# TSOC_Teensy3X.net
KiCad netlist of a schematic drawn in EAGLE
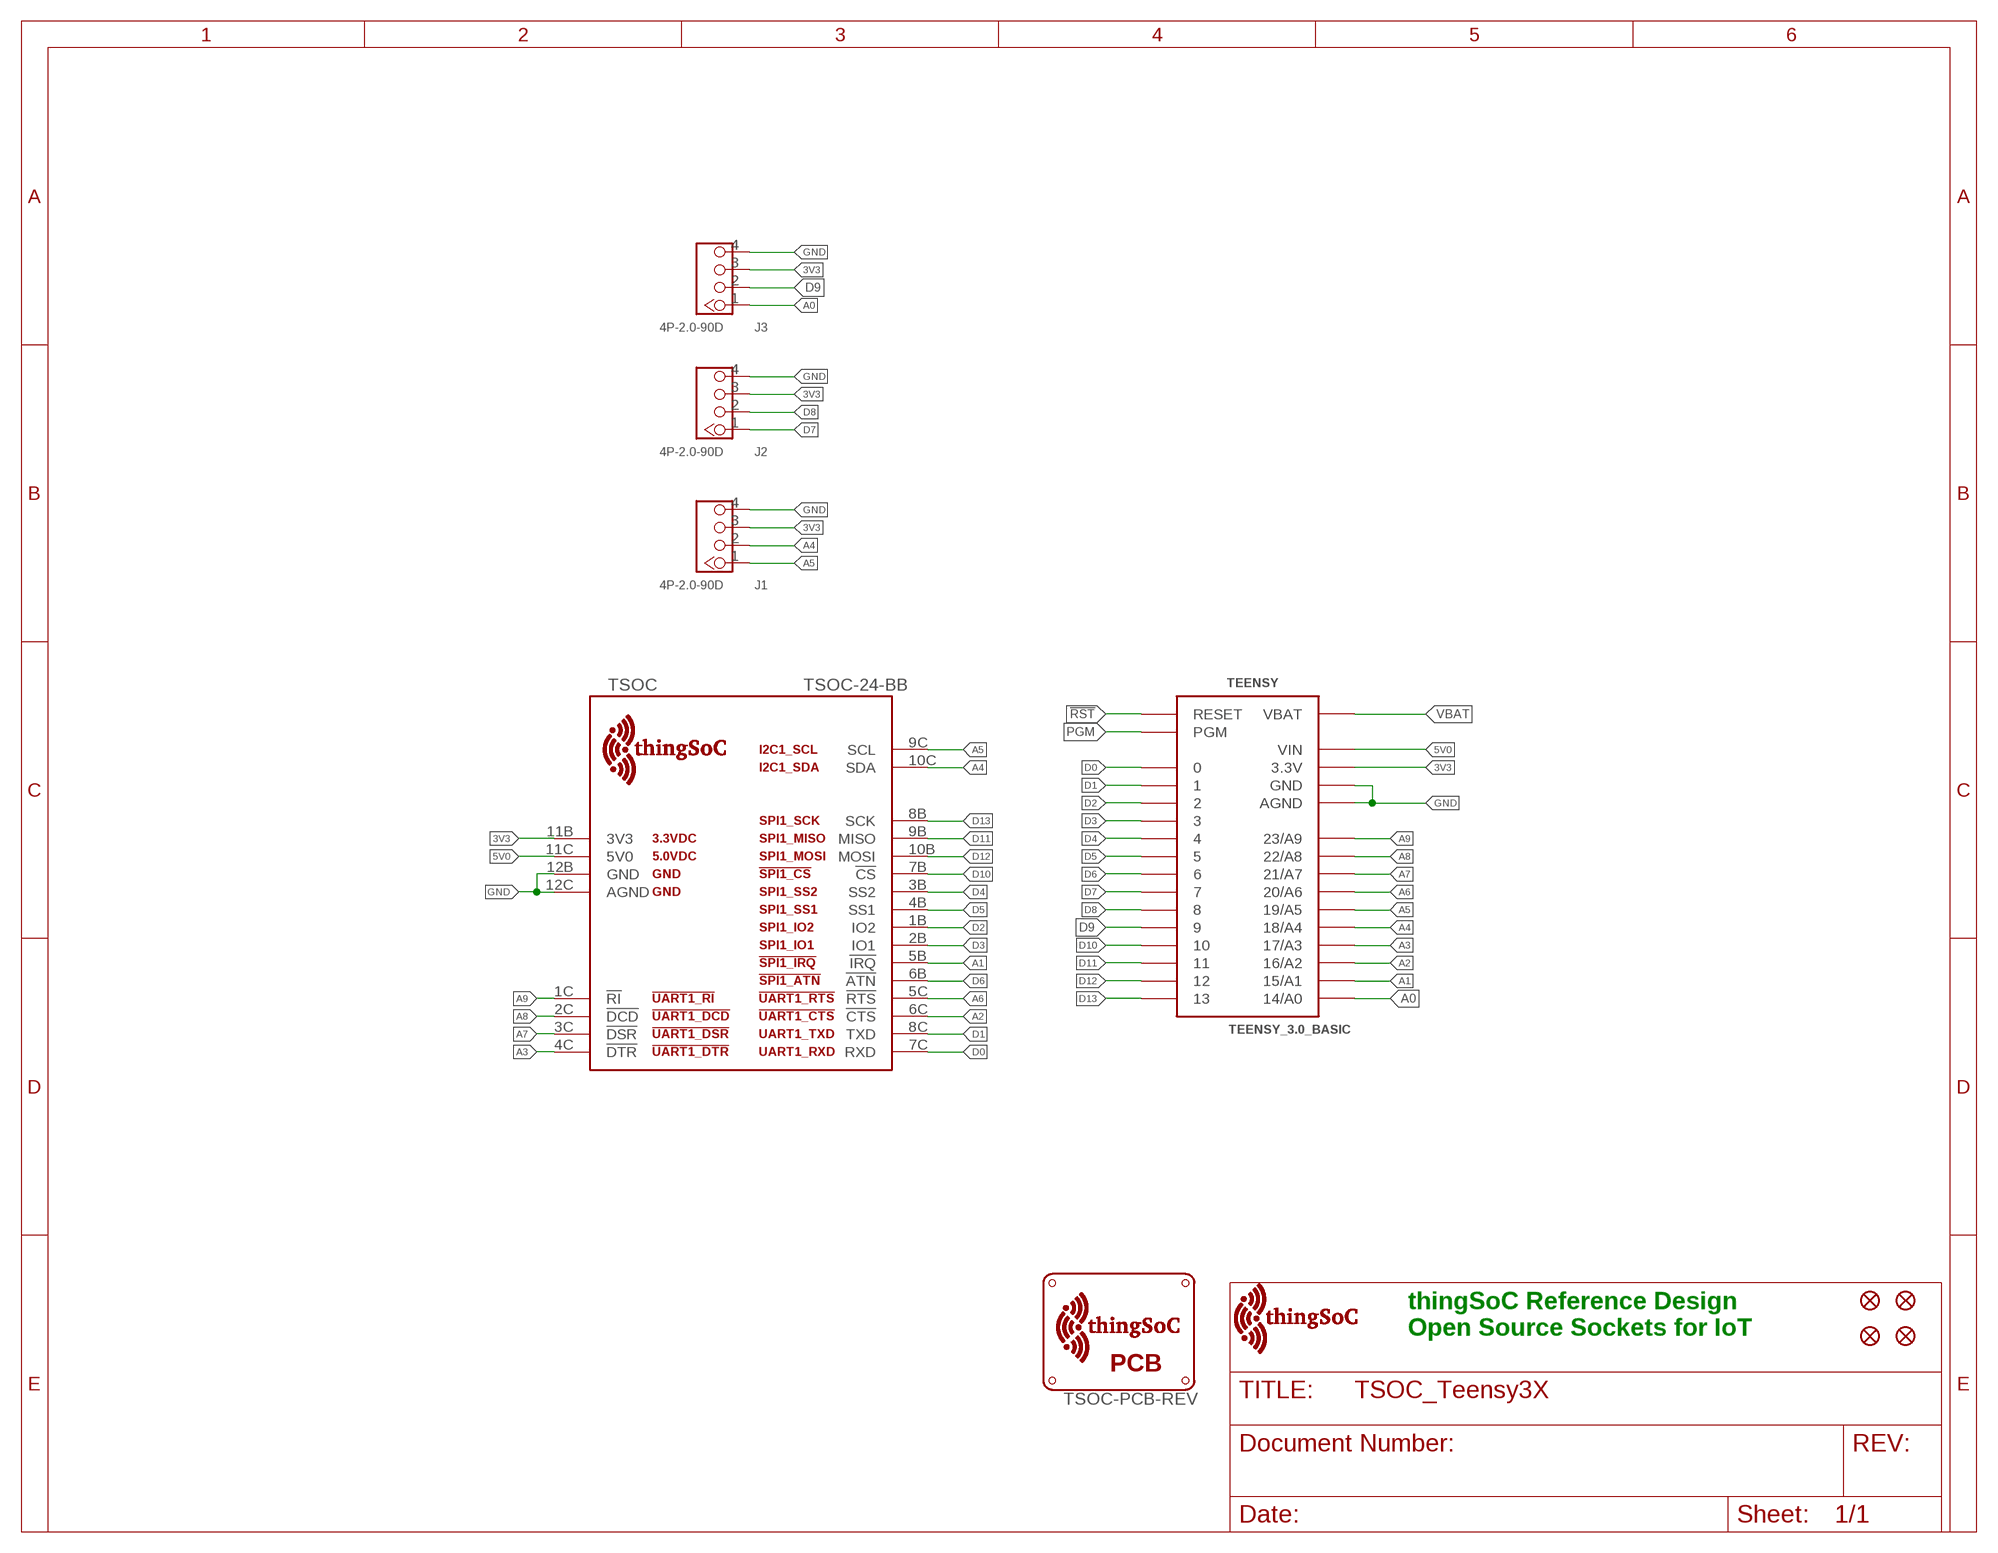
[diagram p0: schematic, sheet 1]

(export (version "E")
  (design (tool "Eeschema 10.0.6"))
  (components
    (comp (ref "FID1")
      (value "FIDUCIALUFIDUCIAL")
      (footprint "eagle-import:MICRO-FIDUCIAL")
      (libsource (lib "eagle-import") (part "FIDUCIALUFIDUCIAL"))
    )
    (comp (ref "FID2")
      (value "FIDUCIALUFIDUCIAL")
      (footprint "eagle-import:MICRO-FIDUCIAL")
      (libsource (lib "eagle-import") (part "FIDUCIALUFIDUCIAL"))
    )
    (comp (ref "FID3")
      (value "FIDUCIALUFIDUCIAL")
      (footprint "eagle-import:MICRO-FIDUCIAL")
      (libsource (lib "eagle-import") (part "FIDUCIALUFIDUCIAL"))
    )
    (comp (ref "FID4")
      (value "FIDUCIALUFIDUCIAL")
      (footprint "eagle-import:MICRO-FIDUCIAL")
      (libsource (lib "eagle-import") (part "FIDUCIALUFIDUCIAL"))
    )
    (comp (ref "J1")
      (value "4P-2.0-90D")
      (footprint "eagle-import:HW4-2.0-90D")
      (libsource (lib "eagle-import") (part "GROVE-CONNECTOR-DIP-90D(4P-2.0)"))
    )
    (comp (ref "J2")
      (value "4P-2.0-90D")
      (footprint "eagle-import:HW4-2.0-90D")
      (libsource (lib "eagle-import") (part "GROVE-CONNECTOR-DIP-90D(4P-2.0)"))
    )
    (comp (ref "J3")
      (value "4P-2.0-90D")
      (footprint "eagle-import:HW4-2.0-90D")
      (libsource (lib "eagle-import") (part "GROVE-CONNECTOR-DIP-90D(4P-2.0)"))
    )
    (comp (ref "TEENSY")
      (value "TEENSY_3.0_BASIC")
      (footprint "eagle-import:TEENSY_3.0_BASIC")
      (libsource (lib "eagle-import") (part "TEENSY_3.0_BASIC"))
    )
    (comp (ref "TSOC")
      (value "TSOC-24-BB")
      (footprint "eagle-import:TSOC-BB-S24")
      (libsource (lib "eagle-import") (part "TSOC-24-BB"))
    )
    (comp (ref "U$2")
      (value "TSOC-PCB-REV")
      (footprint "eagle-import:TSOC-BB-BRD-PLUS-CUT-REV")
      (libsource (lib "eagle-import") (part "TSOC-PCB-REV"))
    )
    (comp (ref "U$5")
      (value "TSOC-LOGO-LRG")
      (footprint "eagle-import:TSOC-LOGO-LRG")
      (libsource (lib "eagle-import") (part "TSOC-LOGO-LRG"))
    )
  )
  (nets
    (net (code "1") (name "/~{RST}") (class "Default")
      (node (ref "TEENSY") (pin "RESET") (pinfunction "RESET_RESET") (pintype "bidirectional"))
    )
    (net (code "2") (name "3V3") (class "Default")
      (node (ref "J1") (pin "3") (pinfunction "3_3") (pintype "bidirectional"))
      (node (ref "J2") (pin "3") (pinfunction "3_3") (pintype "bidirectional"))
      (node (ref "J3") (pin "3") (pinfunction "3_3") (pintype "bidirectional"))
      (node (ref "TEENSY") (pin "3.3V") (pinfunction "3.3V_3.3V") (pintype "power_in"))
      (node (ref "TEENSY") (pin "3.3V1") (pinfunction "3.3V_3.3V1") (pintype "power_in"))
      (node (ref "TSOC") (pin "11B") (pinfunction "3V3_11B") (pintype "bidirectional"))
    )
    (net (code "3") (name "5V0") (class "Default")
      (node (ref "TEENSY") (pin "VIN") (pinfunction "VIN_VIN") (pintype "power_in"))
      (node (ref "TSOC") (pin "11C") (pinfunction "5V0_11C") (pintype "bidirectional"))
    )
    (net (code "4") (name "A0") (class "Default")
      (node (ref "J3") (pin "1") (pinfunction "1_1") (pintype "bidirectional"))
      (node (ref "TEENSY") (pin "14/A0") (pinfunction "14/A0_14/A0") (pintype "bidirectional"))
    )
    (net (code "5") (name "A1") (class "Default")
      (node (ref "TEENSY") (pin "15/A1") (pinfunction "15/A1_15/A1") (pintype "bidirectional"))
      (node (ref "TSOC") (pin "5B") (pinfunction "~{IRQ}_5B") (pintype "bidirectional"))
    )
    (net (code "6") (name "A2") (class "Default")
      (node (ref "TEENSY") (pin "16/A2") (pinfunction "16/A2_16/A2") (pintype "bidirectional"))
      (node (ref "TSOC") (pin "6C") (pinfunction "~{CTS}_6C") (pintype "bidirectional"))
    )
    (net (code "7") (name "A3") (class "Default")
      (node (ref "TEENSY") (pin "17/A3") (pinfunction "17/A3_17/A3") (pintype "bidirectional"))
      (node (ref "TSOC") (pin "4C") (pinfunction "~{DTR}_4C") (pintype "bidirectional"))
    )
    (net (code "8") (name "A4") (class "Default")
      (node (ref "J1") (pin "2") (pinfunction "2_2") (pintype "bidirectional"))
      (node (ref "TEENSY") (pin "18/A4") (pinfunction "18/A4_18/A4") (pintype "bidirectional"))
      (node (ref "TSOC") (pin "10C") (pinfunction "SDA_10C") (pintype "bidirectional"))
    )
    (net (code "9") (name "A5") (class "Default")
      (node (ref "J1") (pin "1") (pinfunction "1_1") (pintype "bidirectional"))
      (node (ref "TEENSY") (pin "19/A5") (pinfunction "19/A5_19/A5") (pintype "bidirectional"))
      (node (ref "TSOC") (pin "9C") (pinfunction "SCL_9C") (pintype "bidirectional"))
    )
    (net (code "10") (name "A6") (class "Default")
      (node (ref "TEENSY") (pin "20/A6") (pinfunction "20/A6_20/A6") (pintype "bidirectional"))
      (node (ref "TSOC") (pin "5C") (pinfunction "~{RTS}_5C") (pintype "bidirectional"))
    )
    (net (code "11") (name "A7") (class "Default")
      (node (ref "TEENSY") (pin "21/A7") (pinfunction "21/A7_21/A7") (pintype "bidirectional"))
      (node (ref "TSOC") (pin "3C") (pinfunction "~{DSR}_3C") (pintype "bidirectional"))
    )
    (net (code "12") (name "A8") (class "Default")
      (node (ref "TEENSY") (pin "22/A8") (pinfunction "22/A8_22/A8") (pintype "bidirectional"))
      (node (ref "TSOC") (pin "2C") (pinfunction "~{DCD}_2C") (pintype "bidirectional"))
    )
    (net (code "13") (name "A9") (class "Default")
      (node (ref "TEENSY") (pin "23/A9") (pinfunction "23/A9_23/A9") (pintype "bidirectional"))
      (node (ref "TSOC") (pin "1C") (pinfunction "~{RI}_1C") (pintype "bidirectional"))
    )
    (net (code "14") (name "D0") (class "Default")
      (node (ref "TEENSY") (pin "0") (pinfunction "0_0") (pintype "bidirectional"))
      (node (ref "TSOC") (pin "7C") (pinfunction "RXD_7C") (pintype "bidirectional"))
    )
    (net (code "15") (name "D1") (class "Default")
      (node (ref "TEENSY") (pin "1") (pinfunction "1_1") (pintype "bidirectional"))
      (node (ref "TSOC") (pin "8C") (pinfunction "TXD_8C") (pintype "bidirectional"))
    )
    (net (code "16") (name "D2") (class "Default")
      (node (ref "TEENSY") (pin "2") (pinfunction "2_2") (pintype "bidirectional"))
      (node (ref "TSOC") (pin "1B") (pinfunction "IO2_1B") (pintype "bidirectional"))
    )
    (net (code "17") (name "D3") (class "Default")
      (node (ref "TEENSY") (pin "3") (pinfunction "3_3") (pintype "bidirectional"))
      (node (ref "TSOC") (pin "2B") (pinfunction "IO1_2B") (pintype "bidirectional"))
    )
    (net (code "18") (name "D4") (class "Default")
      (node (ref "TEENSY") (pin "4") (pinfunction "4_4") (pintype "bidirectional"))
      (node (ref "TSOC") (pin "3B") (pinfunction "SS2_3B") (pintype "bidirectional"))
    )
    (net (code "19") (name "D5") (class "Default")
      (node (ref "TEENSY") (pin "5") (pinfunction "5_5") (pintype "bidirectional"))
      (node (ref "TSOC") (pin "4B") (pinfunction "SS1_4B") (pintype "bidirectional"))
    )
    (net (code "20") (name "D6") (class "Default")
      (node (ref "TEENSY") (pin "6") (pinfunction "6_6") (pintype "bidirectional"))
      (node (ref "TSOC") (pin "6B") (pinfunction "~{ATN}_6B") (pintype "bidirectional"))
    )
    (net (code "21") (name "D7") (class "Default")
      (node (ref "J2") (pin "1") (pinfunction "1_1") (pintype "bidirectional"))
      (node (ref "TEENSY") (pin "7") (pinfunction "7_7") (pintype "bidirectional"))
    )
    (net (code "22") (name "D8") (class "Default")
      (node (ref "J2") (pin "2") (pinfunction "2_2") (pintype "bidirectional"))
      (node (ref "TEENSY") (pin "8") (pinfunction "8_8") (pintype "bidirectional"))
    )
    (net (code "23") (name "D9") (class "Default")
      (node (ref "J3") (pin "2") (pinfunction "2_2") (pintype "bidirectional"))
      (node (ref "TEENSY") (pin "9") (pinfunction "9_9") (pintype "bidirectional"))
    )
    (net (code "24") (name "D10") (class "Default")
      (node (ref "TEENSY") (pin "10") (pinfunction "10_10") (pintype "bidirectional"))
      (node (ref "TSOC") (pin "7B") (pinfunction "~{CS}_7B") (pintype "bidirectional"))
    )
    (net (code "25") (name "D11") (class "Default")
      (node (ref "TEENSY") (pin "11") (pinfunction "11_11") (pintype "bidirectional"))
      (node (ref "TSOC") (pin "9B") (pinfunction "MISO_9B") (pintype "bidirectional"))
    )
    (net (code "26") (name "D12") (class "Default")
      (node (ref "TEENSY") (pin "12") (pinfunction "12_12") (pintype "bidirectional"))
      (node (ref "TSOC") (pin "10B") (pinfunction "MOSI_10B") (pintype "bidirectional"))
    )
    (net (code "27") (name "D13") (class "Default")
      (node (ref "TEENSY") (pin "13") (pinfunction "13_13") (pintype "bidirectional"))
      (node (ref "TSOC") (pin "8B") (pinfunction "SCK_8B") (pintype "bidirectional"))
    )
    (net (code "28") (name "GND") (class "Default")
      (node (ref "J1") (pin "4") (pinfunction "4_4") (pintype "bidirectional"))
      (node (ref "J2") (pin "4") (pinfunction "4_4") (pintype "bidirectional"))
      (node (ref "J3") (pin "4") (pinfunction "4_4") (pintype "bidirectional"))
      (node (ref "TEENSY") (pin "AGND") (pinfunction "AGND_AGND") (pintype "power_in"))
      (node (ref "TEENSY") (pin "GND") (pinfunction "GND_GND") (pintype "power_in"))
      (node (ref "TEENSY") (pin "GND1") (pinfunction "GND_GND1") (pintype "power_in"))
      (node (ref "TSOC") (pin "12B") (pinfunction "GND_12B") (pintype "bidirectional"))
      (node (ref "TSOC") (pin "12C") (pinfunction "AGND_12C") (pintype "bidirectional"))
    )
    (net (code "29") (name "PGM") (class "Default")
      (node (ref "TEENSY") (pin "PGM") (pinfunction "PGM_PGM") (pintype "bidirectional"))
    )
    (net (code "30") (name "VBAT") (class "Default")
      (node (ref "TEENSY") (pin "VBAT") (pinfunction "VBAT_VBAT") (pintype "power_in"))
    )
  )
)
